# 11Dof_BMA180.net
KiCad netlist of a schematic drawn in EAGLE
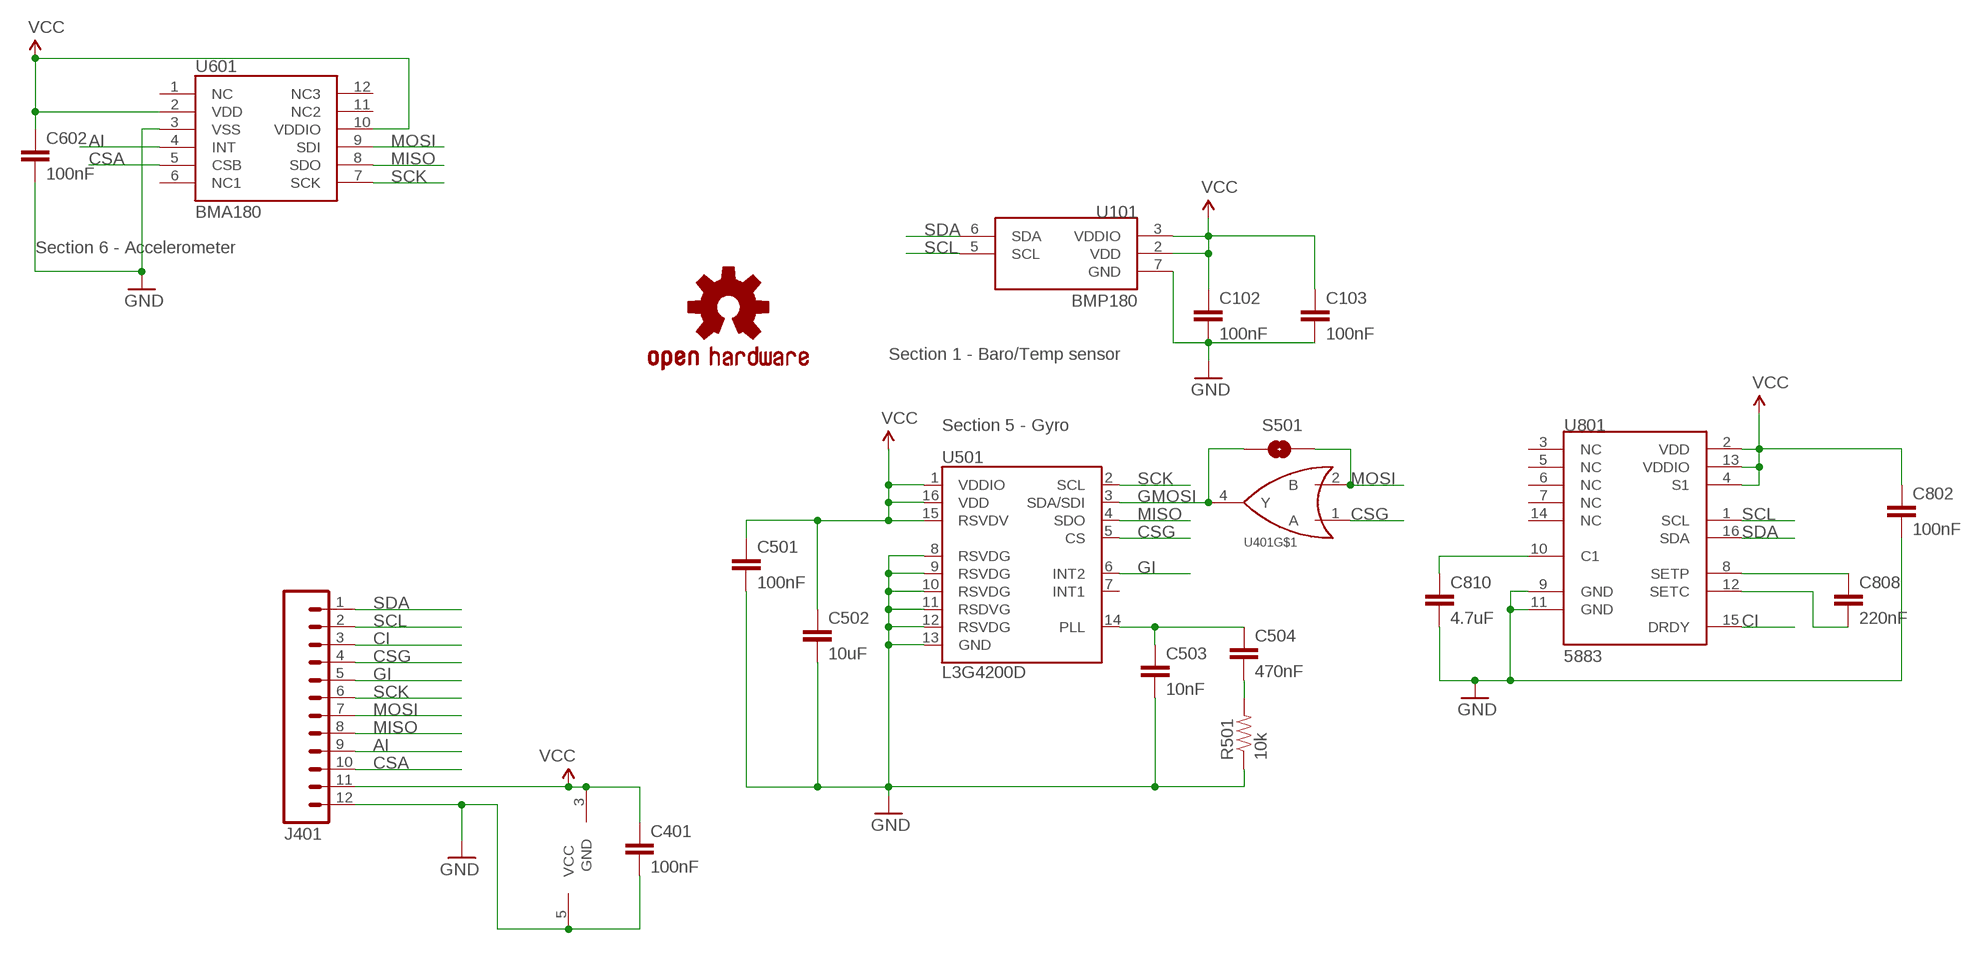
[diagram p0: schematic, sheet 1]

(export (version "E")
  (design (tool "Eeschema 10.0.6"))
  (components
    (comp (ref "C102")
      (value "100nF")
      (footprint "eagle-import:0603-CAP")
      (libsource (lib "eagle-import") (part "CAP0603-CAP"))
    )
    (comp (ref "C103")
      (value "100nF")
      (footprint "eagle-import:0603-CAP")
      (libsource (lib "eagle-import") (part "CAP0603-CAP"))
    )
    (comp (ref "C401")
      (value "100nF")
      (footprint "eagle-import:0603-CAP")
      (libsource (lib "eagle-import") (part "CAP0603-CAP"))
    )
    (comp (ref "C501")
      (value "100nF")
      (footprint "eagle-import:0603-CAP")
      (libsource (lib "eagle-import") (part "CAP0603-CAP"))
    )
    (comp (ref "C502")
      (value "10uF")
      (footprint "eagle-import:0603-CAP")
      (libsource (lib "eagle-import") (part "CAP0603-CAP"))
    )
    (comp (ref "C503")
      (value "10nF")
      (footprint "eagle-import:0603-CAP")
      (libsource (lib "eagle-import") (part "CAP0603-CAP"))
    )
    (comp (ref "C504")
      (value "470nF")
      (footprint "eagle-import:0603-CAP")
      (libsource (lib "eagle-import") (part "CAP0603-CAP"))
    )
    (comp (ref "C602")
      (value "100nF")
      (footprint "eagle-import:0603-CAP")
      (libsource (lib "eagle-import") (part "CAP0603-CAP"))
    )
    (comp (ref "C802")
      (value "100nF")
      (footprint "eagle-import:0603-CAP")
      (libsource (lib "eagle-import") (part "CAP0603-CAP"))
    )
    (comp (ref "C808")
      (value "220nF")
      (footprint "eagle-import:0603-CAP")
      (libsource (lib "eagle-import") (part "CAP0603-CAP"))
    )
    (comp (ref "C810")
      (value "4.7uF")
      (footprint "eagle-import:0603-CAP")
      (libsource (lib "eagle-import") (part "CAP0603-CAP"))
    )
    (comp (ref "J401")
      (value "M12PTH")
      (footprint "eagle-import:1X12")
      (libsource (lib "eagle-import") (part "M12PTH"))
    )
    (comp (ref "R501")
      (value "10k")
      (footprint "eagle-import:0603-RES")
      (libsource (lib "eagle-import") (part "RESISTOR0603-RES"))
    )
    (comp (ref "S501")
      (value "SOLDERJUMPERNO")
      (footprint "eagle-import:SJ_2S-NO")
      (libsource (lib "eagle-import") (part "SOLDERJUMPERNO"))
    )
    (comp (ref "U$2")
      (value "OSHW-LOGOS")
      (footprint "eagle-import:OSHW-LOGO-S")
      (libsource (lib "eagle-import") (part "OSHW-LOGOS"))
    )
    (comp (ref "U101")
      (value "BMP180")
      (footprint "eagle-import:BMP180")
      (libsource (lib "eagle-import") (part "BMP180"))
    )
    (comp (ref "U401")
      (value "SN74LVC1G32")
      (footprint "eagle-import:SOT-23-5")
      (fields (field (name "DIGIKEY") "296-9847-2-ND"))
      (libsource (lib "eagle-import") (part "SN74LVC1G32"))
    )
    (comp (ref "U501")
      (value "L3G4200D")
      (footprint "eagle-import:LGA16-4X4")
      (libsource (lib "eagle-import") (part "L3G4200D"))
    )
    (comp (ref "U601")
      (value "BMA180")
      (footprint "eagle-import:LGA12")
      (libsource (lib "eagle-import") (part "BMA180"))
    )
    (comp (ref "U801")
      (value "5883")
      (footprint "eagle-import:16LPCC")
      (libsource (lib "eagle-import") (part "HMC5883LSMD"))
    )
  )
  (nets
    (net (code "1") (name "/AI") (class "Default")
      (node (ref "J401") (pin "9") (pinfunction "9_9") (pintype "passive"))
      (node (ref "U601") (pin "4") (pinfunction "INT_4") (pintype "bidirectional"))
    )
    (net (code "2") (name "/CI") (class "Default")
      (node (ref "J401") (pin "3") (pinfunction "3_3") (pintype "passive"))
      (node (ref "U801") (pin "15") (pinfunction "DRDY_15") (pintype "bidirectional"))
    )
    (net (code "3") (name "/CSA") (class "Default")
      (node (ref "J401") (pin "10") (pinfunction "10_10") (pintype "passive"))
      (node (ref "U601") (pin "5") (pinfunction "CSB_5") (pintype "bidirectional"))
    )
    (net (code "4") (name "/CSG") (class "Default")
      (node (ref "J401") (pin "4") (pinfunction "4_4") (pintype "passive"))
      (node (ref "U401") (pin "1") (pinfunction "A_1") (pintype "bidirectional"))
      (node (ref "U501") (pin "5") (pinfunction "CS_5") (pintype "bidirectional"))
    )
    (net (code "5") (name "/GI") (class "Default")
      (node (ref "J401") (pin "5") (pinfunction "5_5") (pintype "passive"))
      (node (ref "U501") (pin "6") (pinfunction "INT2_6") (pintype "bidirectional"))
    )
    (net (code "6") (name "/GMOSI") (class "Default")
      (node (ref "S501") (pin "1") (pinfunction "1_1") (pintype "passive"))
      (node (ref "U401") (pin "4") (pinfunction "Y_4") (pintype "bidirectional"))
      (node (ref "U501") (pin "3") (pinfunction "SDA/SDI_3") (pintype "bidirectional"))
    )
    (net (code "7") (name "/MISO") (class "Default")
      (node (ref "J401") (pin "8") (pinfunction "8_8") (pintype "passive"))
      (node (ref "U501") (pin "4") (pinfunction "SDO_4") (pintype "bidirectional"))
      (node (ref "U601") (pin "8") (pinfunction "SDO_8") (pintype "bidirectional"))
    )
    (net (code "8") (name "/MOSI") (class "Default")
      (node (ref "J401") (pin "7") (pinfunction "7_7") (pintype "passive"))
      (node (ref "S501") (pin "2") (pinfunction "2_2") (pintype "passive"))
      (node (ref "U401") (pin "2") (pinfunction "B_2") (pintype "bidirectional"))
      (node (ref "U601") (pin "9") (pinfunction "SDI_9") (pintype "bidirectional"))
    )
    (net (code "9") (name "/SCK") (class "Default")
      (node (ref "J401") (pin "6") (pinfunction "6_6") (pintype "passive"))
      (node (ref "U501") (pin "2") (pinfunction "SCL_2") (pintype "bidirectional"))
      (node (ref "U601") (pin "7") (pinfunction "SCK_7") (pintype "bidirectional"))
    )
    (net (code "10") (name "/SCL") (class "Default")
      (node (ref "J401") (pin "2") (pinfunction "2_2") (pintype "passive"))
      (node (ref "U101") (pin "5") (pinfunction "SCL_5") (pintype "input"))
      (node (ref "U801") (pin "1") (pinfunction "SCL_1") (pintype "bidirectional"))
    )
    (net (code "11") (name "/SDA") (class "Default")
      (node (ref "J401") (pin "1") (pinfunction "1_1") (pintype "passive"))
      (node (ref "U101") (pin "6") (pinfunction "SDA_6") (pintype "bidirectional"))
      (node (ref "U801") (pin "16") (pinfunction "SDA_16") (pintype "bidirectional"))
    )
    (net (code "12") (name "GND") (class "Default")
      (node (ref "C102") (pin "2") (pinfunction "2_2") (pintype "passive"))
      (node (ref "C103") (pin "2") (pinfunction "2_2") (pintype "passive"))
      (node (ref "C401") (pin "2") (pinfunction "2_2") (pintype "passive"))
      (node (ref "C501") (pin "2") (pinfunction "2_2") (pintype "passive"))
      (node (ref "C502") (pin "2") (pinfunction "2_2") (pintype "passive"))
      (node (ref "C503") (pin "2") (pinfunction "2_2") (pintype "passive"))
      (node (ref "C602") (pin "2") (pinfunction "2_2") (pintype "passive"))
      (node (ref "C802") (pin "2") (pinfunction "2_2") (pintype "passive"))
      (node (ref "C810") (pin "2") (pinfunction "2_2") (pintype "passive"))
      (node (ref "J401") (pin "12") (pinfunction "12_12") (pintype "passive"))
      (node (ref "R501") (pin "1") (pinfunction "1_1") (pintype "passive"))
      (node (ref "U101") (pin "7") (pinfunction "GND_7") (pintype "power_in"))
      (node (ref "U401") (pin "5") (pinfunction "VCC_5") (pintype "bidirectional"))
      (node (ref "U501") (pin "10") (pinfunction "RSVDG_10") (pintype "bidirectional"))
      (node (ref "U501") (pin "11") (pinfunction "RSDVG_11") (pintype "bidirectional"))
      (node (ref "U501") (pin "12") (pinfunction "RSVDG_12") (pintype "bidirectional"))
      (node (ref "U501") (pin "13") (pinfunction "GND_13") (pintype "bidirectional"))
      (node (ref "U501") (pin "8") (pinfunction "RSVDG_8") (pintype "bidirectional"))
      (node (ref "U501") (pin "9") (pinfunction "RSVDG_9") (pintype "bidirectional"))
      (node (ref "U601") (pin "3") (pinfunction "VSS_3") (pintype "bidirectional"))
      (node (ref "U801") (pin "11") (pinfunction "GND_11") (pintype "bidirectional"))
      (node (ref "U801") (pin "9") (pinfunction "GND_9") (pintype "bidirectional"))
    )
    (net (code "13") (name "Net-(C504-Pad2)") (class "Default")
      (node (ref "C504") (pin "2") (pinfunction "2_2") (pintype "passive"))
      (node (ref "R501") (pin "2") (pinfunction "2_2") (pintype "passive"))
    )
    (net (code "14") (name "Net-(U501-PLL)") (class "Default")
      (node (ref "C503") (pin "1") (pinfunction "1_1") (pintype "passive"))
      (node (ref "C504") (pin "1") (pinfunction "1_1") (pintype "passive"))
      (node (ref "U501") (pin "14") (pinfunction "PLL_14") (pintype "bidirectional"))
    )
    (net (code "15") (name "Net-(U801-C1)") (class "Default")
      (node (ref "C810") (pin "1") (pinfunction "1_1") (pintype "passive"))
      (node (ref "U801") (pin "10") (pinfunction "C1_10") (pintype "bidirectional"))
    )
    (net (code "16") (name "Net-(U801-SETC)") (class "Default")
      (node (ref "C808") (pin "2") (pinfunction "2_2") (pintype "passive"))
      (node (ref "U801") (pin "12") (pinfunction "SETC_12") (pintype "bidirectional"))
    )
    (net (code "17") (name "Net-(U801-SETP)") (class "Default")
      (node (ref "C808") (pin "1") (pinfunction "1_1") (pintype "passive"))
      (node (ref "U801") (pin "8") (pinfunction "SETP_8") (pintype "bidirectional"))
    )
    (net (code "18") (name "VCC") (class "Default")
      (node (ref "C102") (pin "1") (pinfunction "1_1") (pintype "passive"))
      (node (ref "C103") (pin "1") (pinfunction "1_1") (pintype "passive"))
      (node (ref "C401") (pin "1") (pinfunction "1_1") (pintype "passive"))
      (node (ref "C501") (pin "1") (pinfunction "1_1") (pintype "passive"))
      (node (ref "C502") (pin "1") (pinfunction "1_1") (pintype "passive"))
      (node (ref "C602") (pin "1") (pinfunction "1_1") (pintype "passive"))
      (node (ref "C802") (pin "1") (pinfunction "1_1") (pintype "passive"))
      (node (ref "J401") (pin "11") (pinfunction "11_11") (pintype "passive"))
      (node (ref "U101") (pin "2") (pinfunction "VDD_2") (pintype "power_in"))
      (node (ref "U101") (pin "3") (pinfunction "VDDIO_3") (pintype "power_in"))
      (node (ref "U401") (pin "3") (pinfunction "GND_3") (pintype "bidirectional"))
      (node (ref "U501") (pin "1") (pinfunction "VDDIO_1") (pintype "bidirectional"))
      (node (ref "U501") (pin "15") (pinfunction "RSVDV_15") (pintype "bidirectional"))
      (node (ref "U501") (pin "16") (pinfunction "VDD_16") (pintype "bidirectional"))
      (node (ref "U601") (pin "10") (pinfunction "VDDIO_10") (pintype "bidirectional"))
      (node (ref "U601") (pin "2") (pinfunction "VDD_2") (pintype "bidirectional"))
      (node (ref "U801") (pin "13") (pinfunction "VDDIO_13") (pintype "bidirectional"))
      (node (ref "U801") (pin "2") (pinfunction "VDD_2") (pintype "bidirectional"))
      (node (ref "U801") (pin "4") (pinfunction "S1_4") (pintype "bidirectional"))
    )
    (net (code "19") (name "unconnected-(U501-INT1-Pad7)") (class "Default")
      (node (ref "U501") (pin "7") (pinfunction "INT1_7") (pintype "bidirectional"))
    )
    (net (code "20") (name "unconnected-(U601-NC-Pad1)") (class "Default")
      (node (ref "U601") (pin "1") (pinfunction "NC_1") (pintype "bidirectional"))
    )
    (net (code "21") (name "unconnected-(U601-NC1-Pad6)") (class "Default")
      (node (ref "U601") (pin "6") (pinfunction "NC1_6") (pintype "bidirectional"))
    )
    (net (code "22") (name "unconnected-(U601-NC2-Pad11)") (class "Default")
      (node (ref "U601") (pin "11") (pinfunction "NC2_11") (pintype "bidirectional"))
    )
    (net (code "23") (name "unconnected-(U601-NC3-Pad12)") (class "Default")
      (node (ref "U601") (pin "12") (pinfunction "NC3_12") (pintype "bidirectional"))
    )
    (net (code "24") (name "unconnected-(U801-NC-Pad3)") (class "Default")
      (node (ref "U801") (pin "3") (pinfunction "NC_3") (pintype "bidirectional"))
    )
    (net (code "25") (name "unconnected-(U801-NC-Pad5)") (class "Default")
      (node (ref "U801") (pin "5") (pinfunction "NC_5") (pintype "bidirectional"))
    )
    (net (code "26") (name "unconnected-(U801-NC-Pad6)") (class "Default")
      (node (ref "U801") (pin "6") (pinfunction "NC_6") (pintype "bidirectional"))
    )
    (net (code "27") (name "unconnected-(U801-NC-Pad7)") (class "Default")
      (node (ref "U801") (pin "7") (pinfunction "NC_7") (pintype "bidirectional"))
    )
    (net (code "28") (name "unconnected-(U801-NC-Pad14)") (class "Default")
      (node (ref "U801") (pin "14") (pinfunction "NC_14") (pintype "bidirectional"))
    )
  )
)
